# breakout.net
KiCad netlist of a schematic drawn in EAGLE
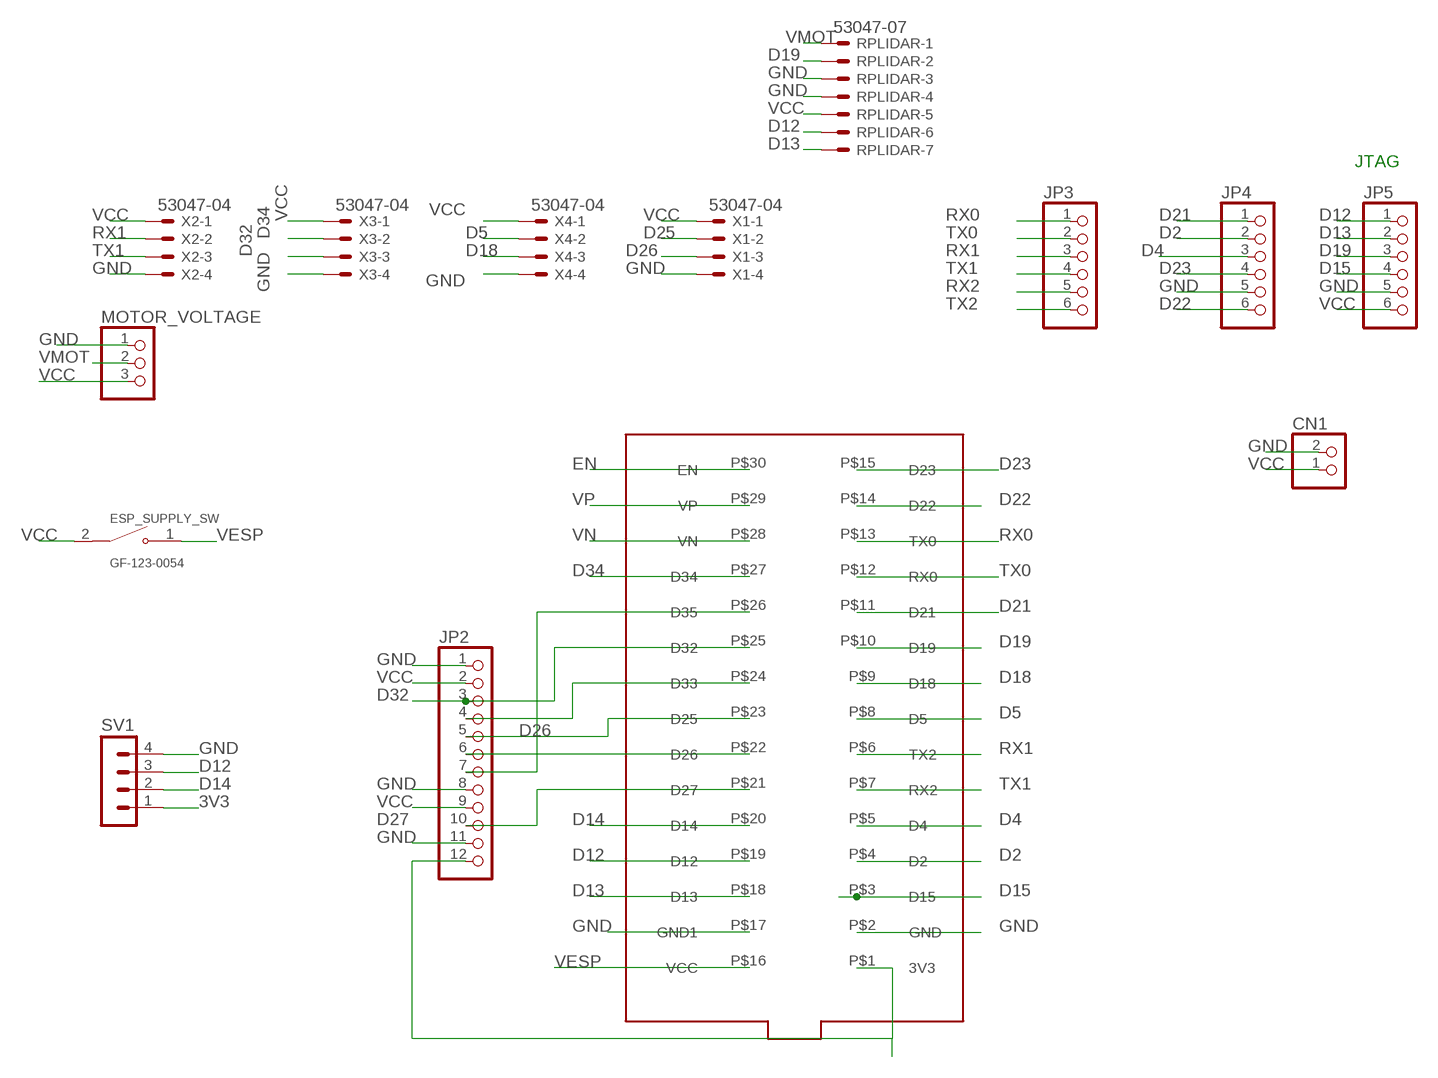
[diagram p0: schematic, sheet 1]

(export (version "E")
  (design (tool "Eeschema 10.0.6"))
  (components
    (comp (ref "CN1")
      (value "JST_2PIN-THM")
      (footprint "eagle-import:JST-PH-2-THM")
      (libsource (lib "eagle-import") (part "JST_2PIN-THM"))
    )
    (comp (ref "ESP_SUPPLY_SW")
      (value "GF-123-0054")
      (footprint "eagle-import:SW_GF-123-0054")
      (fields (field (name "MF") "CW Industries"))
      (libsource (lib "eagle-import") (part "GF-123-0054"))
    )
    (comp (ref "JP2")
      (value "PINHD-1X12")
      (footprint "eagle-import:1X12")
      (libsource (lib "eagle-import") (part "PINHD-1X12"))
    )
    (comp (ref "JP3")
      (value "PINHD-1X6")
      (footprint "eagle-import:1X06")
      (libsource (lib "eagle-import") (part "PINHD-1X6"))
    )
    (comp (ref "JP4")
      (value "PINHD-1X6")
      (footprint "eagle-import:1X06")
      (libsource (lib "eagle-import") (part "PINHD-1X6"))
    )
    (comp (ref "JP5")
      (value "PINHD-1X6")
      (footprint "eagle-import:1X06")
      (libsource (lib "eagle-import") (part "PINHD-1X6"))
    )
    (comp (ref "MOTOR_VOLTAGE")
      (value "PINHD-1X3")
      (footprint "eagle-import:1X03")
      (libsource (lib "eagle-import") (part "PINHD-1X3"))
    )
    (comp (ref "RPLIDAR")
      (value "53047-07")
      (footprint "eagle-import:53047-07")
      (fields (field (name "MF") "MOLEX") (field (name "MPN") "53047-0710-C"))
      (libsource (lib "eagle-import") (part "53?-07047"))
    )
    (comp (ref "SV1")
      (value "MA04-1")
      (footprint "eagle-import:MA04-1")
      (libsource (lib "eagle-import") (part "MA04-1"))
    )
    (comp (ref "U$1")
      (value "ESP-32_30P_BKOUT")
      (footprint "eagle-import:ESP32-30P")
      (libsource (lib "eagle-import") (part "ESP-32_30P_BKOUT"))
    )
    (comp (ref "X1")
      (value "53047-04")
      (footprint "eagle-import:53047-04")
      (fields (field (name "MF") "WALDOM/MOLEX") (field (name "MPN") "53047-0410"))
      (libsource (lib "eagle-import") (part "53?-04047"))
    )
    (comp (ref "X2")
      (value "53047-04")
      (footprint "eagle-import:53047-04")
      (fields (field (name "MF") "WALDOM/MOLEX") (field (name "MPN") "53047-0410"))
      (libsource (lib "eagle-import") (part "53?-04047"))
    )
    (comp (ref "X3")
      (value "53047-04")
      (footprint "eagle-import:53047-04")
      (fields (field (name "MF") "WALDOM/MOLEX") (field (name "MPN") "53047-0410"))
      (libsource (lib "eagle-import") (part "53?-04047"))
    )
    (comp (ref "X4")
      (value "53047-04")
      (footprint "eagle-import:53047-04")
      (fields (field (name "MF") "WALDOM/MOLEX") (field (name "MPN") "53047-0410"))
      (libsource (lib "eagle-import") (part "53?-04047"))
    )
  )
  (nets
    (net (code "1") (name "/3V3") (class "Default")
      (node (ref "SV1") (pin "1") (pinfunction "1_1") (pintype "passive"))
    )
    (net (code "2") (name "/D2") (class "Default")
      (node (ref "JP4") (pin "2") (pinfunction "2_2") (pintype "passive"))
      (node (ref "U$1") (pin "P$4") (pinfunction "D2_P$4") (pintype "bidirectional"))
    )
    (net (code "3") (name "/D4") (class "Default")
      (node (ref "JP4") (pin "3") (pinfunction "3_3") (pintype "passive"))
      (node (ref "U$1") (pin "P$5") (pinfunction "D4_P$5") (pintype "bidirectional"))
    )
    (net (code "4") (name "/D5") (class "Default")
      (node (ref "U$1") (pin "P$8") (pinfunction "D5_P$8") (pintype "bidirectional"))
      (node (ref "X4") (pin "2") (pinfunction "S_2") (pintype "passive"))
    )
    (net (code "5") (name "/D12") (class "Default")
      (node (ref "JP5") (pin "1") (pinfunction "1_1") (pintype "passive"))
      (node (ref "RPLIDAR") (pin "6") (pinfunction "S_6") (pintype "passive"))
      (node (ref "SV1") (pin "3") (pinfunction "3_3") (pintype "passive"))
      (node (ref "U$1") (pin "P$19") (pinfunction "D12_P$19") (pintype "bidirectional"))
    )
    (net (code "6") (name "/D13") (class "Default")
      (node (ref "JP5") (pin "2") (pinfunction "2_2") (pintype "passive"))
      (node (ref "RPLIDAR") (pin "7") (pinfunction "S_7") (pintype "passive"))
      (node (ref "U$1") (pin "P$18") (pinfunction "D13_P$18") (pintype "bidirectional"))
    )
    (net (code "7") (name "/D14") (class "Default")
      (node (ref "SV1") (pin "2") (pinfunction "2_2") (pintype "passive"))
      (node (ref "U$1") (pin "P$20") (pinfunction "D14_P$20") (pintype "bidirectional"))
    )
    (net (code "8") (name "/D15") (class "Default")
      (node (ref "JP5") (pin "4") (pinfunction "4_4") (pintype "passive"))
      (node (ref "U$1") (pin "P$3") (pinfunction "D15_P$3") (pintype "bidirectional"))
    )
    (net (code "9") (name "/D18") (class "Default")
      (node (ref "U$1") (pin "P$9") (pinfunction "D18_P$9") (pintype "bidirectional"))
      (node (ref "X4") (pin "3") (pinfunction "S_3") (pintype "passive"))
    )
    (net (code "10") (name "/D19") (class "Default")
      (node (ref "JP5") (pin "3") (pinfunction "3_3") (pintype "passive"))
      (node (ref "RPLIDAR") (pin "2") (pinfunction "S_2") (pintype "passive"))
      (node (ref "U$1") (pin "P$10") (pinfunction "D19_P$10") (pintype "bidirectional"))
    )
    (net (code "11") (name "/D21") (class "Default")
      (node (ref "JP4") (pin "1") (pinfunction "1_1") (pintype "passive"))
      (node (ref "U$1") (pin "P$11") (pinfunction "D21_P$11") (pintype "bidirectional"))
    )
    (net (code "12") (name "/D22") (class "Default")
      (node (ref "JP4") (pin "6") (pinfunction "6_6") (pintype "passive"))
      (node (ref "U$1") (pin "P$14") (pinfunction "D22_P$14") (pintype "bidirectional"))
    )
    (net (code "13") (name "/D23") (class "Default")
      (node (ref "JP4") (pin "4") (pinfunction "4_4") (pintype "passive"))
      (node (ref "U$1") (pin "P$15") (pinfunction "D23_P$15") (pintype "bidirectional"))
    )
    (net (code "14") (name "/D25") (class "Default")
      (node (ref "JP2") (pin "5") (pinfunction "5_5") (pintype "passive"))
      (node (ref "U$1") (pin "P$23") (pinfunction "D25_P$23") (pintype "bidirectional"))
      (node (ref "X1") (pin "2") (pinfunction "S_2") (pintype "passive"))
    )
    (net (code "15") (name "/D26") (class "Default")
      (node (ref "JP2") (pin "6") (pinfunction "6_6") (pintype "passive"))
      (node (ref "U$1") (pin "P$22") (pinfunction "D26_P$22") (pintype "bidirectional"))
      (node (ref "X1") (pin "3") (pinfunction "S_3") (pintype "passive"))
    )
    (net (code "16") (name "/D27") (class "Default")
      (node (ref "JP2") (pin "10") (pinfunction "10_10") (pintype "passive"))
      (node (ref "U$1") (pin "P$21") (pinfunction "D27_P$21") (pintype "bidirectional"))
    )
    (net (code "17") (name "/D32") (class "Default")
      (node (ref "JP2") (pin "3") (pinfunction "3_3") (pintype "passive"))
      (node (ref "U$1") (pin "P$25") (pinfunction "D32_P$25") (pintype "bidirectional"))
      (node (ref "X3") (pin "3") (pinfunction "S_3") (pintype "passive"))
    )
    (net (code "18") (name "/D34") (class "Default")
      (node (ref "U$1") (pin "P$27") (pinfunction "D34_P$27") (pintype "bidirectional"))
      (node (ref "X3") (pin "2") (pinfunction "S_2") (pintype "passive"))
    )
    (net (code "19") (name "/EN") (class "Default")
      (node (ref "U$1") (pin "P$30") (pinfunction "EN_P$30") (pintype "bidirectional"))
    )
    (net (code "20") (name "/GND") (class "Default")
      (node (ref "CN1") (pin "2") (pinfunction "1_2") (pintype "passive"))
      (node (ref "JP2") (pin "1") (pinfunction "1_1") (pintype "passive"))
      (node (ref "JP2") (pin "11") (pinfunction "11_11") (pintype "passive"))
      (node (ref "JP2") (pin "8") (pinfunction "8_8") (pintype "passive"))
      (node (ref "JP4") (pin "5") (pinfunction "5_5") (pintype "passive"))
      (node (ref "JP5") (pin "5") (pinfunction "5_5") (pintype "passive"))
      (node (ref "MOTOR_VOLTAGE") (pin "1") (pinfunction "1_1") (pintype "passive"))
      (node (ref "RPLIDAR") (pin "3") (pinfunction "S_3") (pintype "passive"))
      (node (ref "RPLIDAR") (pin "4") (pinfunction "S_4") (pintype "passive"))
      (node (ref "SV1") (pin "4") (pinfunction "4_4") (pintype "passive"))
      (node (ref "U$1") (pin "P$17") (pinfunction "GND1_P$17") (pintype "bidirectional"))
      (node (ref "U$1") (pin "P$2") (pinfunction "GND_P$2") (pintype "bidirectional"))
      (node (ref "X1") (pin "4") (pinfunction "S_4") (pintype "passive"))
      (node (ref "X2") (pin "4") (pinfunction "S_4") (pintype "passive"))
      (node (ref "X3") (pin "4") (pinfunction "S_4") (pintype "passive"))
      (node (ref "X4") (pin "4") (pinfunction "S_4") (pintype "passive"))
    )
    (net (code "21") (name "/RX0") (class "Default")
      (node (ref "JP3") (pin "1") (pinfunction "1_1") (pintype "passive"))
      (node (ref "U$1") (pin "P$13") (pinfunction "TX0_P$13") (pintype "bidirectional"))
    )
    (net (code "22") (name "/RX1") (class "Default")
      (node (ref "JP3") (pin "3") (pinfunction "3_3") (pintype "passive"))
      (node (ref "U$1") (pin "P$6") (pinfunction "TX2_P$6") (pintype "bidirectional"))
      (node (ref "X2") (pin "2") (pinfunction "S_2") (pintype "passive"))
    )
    (net (code "23") (name "/RX2") (class "Default")
      (node (ref "JP3") (pin "5") (pinfunction "5_5") (pintype "passive"))
    )
    (net (code "24") (name "/TX0") (class "Default")
      (node (ref "JP3") (pin "2") (pinfunction "2_2") (pintype "passive"))
      (node (ref "U$1") (pin "P$12") (pinfunction "RX0_P$12") (pintype "bidirectional"))
    )
    (net (code "25") (name "/TX1") (class "Default")
      (node (ref "JP3") (pin "4") (pinfunction "4_4") (pintype "passive"))
      (node (ref "U$1") (pin "P$7") (pinfunction "RX2_P$7") (pintype "bidirectional"))
      (node (ref "X2") (pin "3") (pinfunction "S_3") (pintype "passive"))
    )
    (net (code "26") (name "/TX2") (class "Default")
      (node (ref "JP3") (pin "6") (pinfunction "6_6") (pintype "passive"))
    )
    (net (code "27") (name "/VCC") (class "Default")
      (node (ref "CN1") (pin "1") (pinfunction "2_1") (pintype "passive"))
      (node (ref "ESP_SUPPLY_SW") (pin "2") (pinfunction "2_2") (pintype "passive"))
      (node (ref "JP2") (pin "2") (pinfunction "2_2") (pintype "passive"))
      (node (ref "JP2") (pin "9") (pinfunction "9_9") (pintype "passive"))
      (node (ref "JP5") (pin "6") (pinfunction "6_6") (pintype "passive"))
      (node (ref "MOTOR_VOLTAGE") (pin "3") (pinfunction "3_3") (pintype "passive"))
      (node (ref "RPLIDAR") (pin "5") (pinfunction "S_5") (pintype "passive"))
      (node (ref "X1") (pin "1") (pinfunction "S_1") (pintype "passive"))
      (node (ref "X2") (pin "1") (pinfunction "S_1") (pintype "passive"))
      (node (ref "X3") (pin "1") (pinfunction "S_1") (pintype "passive"))
      (node (ref "X4") (pin "1") (pinfunction "S_1") (pintype "passive"))
    )
    (net (code "28") (name "/VESP") (class "Default")
      (node (ref "ESP_SUPPLY_SW") (pin "1") (pinfunction "1_1") (pintype "passive"))
      (node (ref "U$1") (pin "P$16") (pinfunction "VCC_P$16") (pintype "bidirectional"))
    )
    (net (code "29") (name "/VMOT") (class "Default")
      (node (ref "MOTOR_VOLTAGE") (pin "2") (pinfunction "2_2") (pintype "passive"))
      (node (ref "RPLIDAR") (pin "1") (pinfunction "S_1") (pintype "passive"))
    )
    (net (code "30") (name "/VN") (class "Default")
      (node (ref "U$1") (pin "P$28") (pinfunction "VN_P$28") (pintype "bidirectional"))
    )
    (net (code "31") (name "/VP") (class "Default")
      (node (ref "U$1") (pin "P$29") (pinfunction "VP_P$29") (pintype "bidirectional"))
    )
    (net (code "32") (name "Net-(U$1-3V3)") (class "Default")
      (node (ref "JP2") (pin "12") (pinfunction "12_12") (pintype "passive"))
      (node (ref "U$1") (pin "P$1") (pinfunction "3V3_P$1") (pintype "bidirectional"))
    )
    (net (code "33") (name "Net-(U$1-D33)") (class "Default")
      (node (ref "JP2") (pin "4") (pinfunction "4_4") (pintype "passive"))
      (node (ref "U$1") (pin "P$24") (pinfunction "D33_P$24") (pintype "bidirectional"))
    )
    (net (code "34") (name "Net-(U$1-D35)") (class "Default")
      (node (ref "JP2") (pin "7") (pinfunction "7_7") (pintype "passive"))
      (node (ref "U$1") (pin "P$26") (pinfunction "D35_P$26") (pintype "bidirectional"))
    )
  )
)
